# MCU.net
KiCad netlist of a schematic drawn in Altium Designer
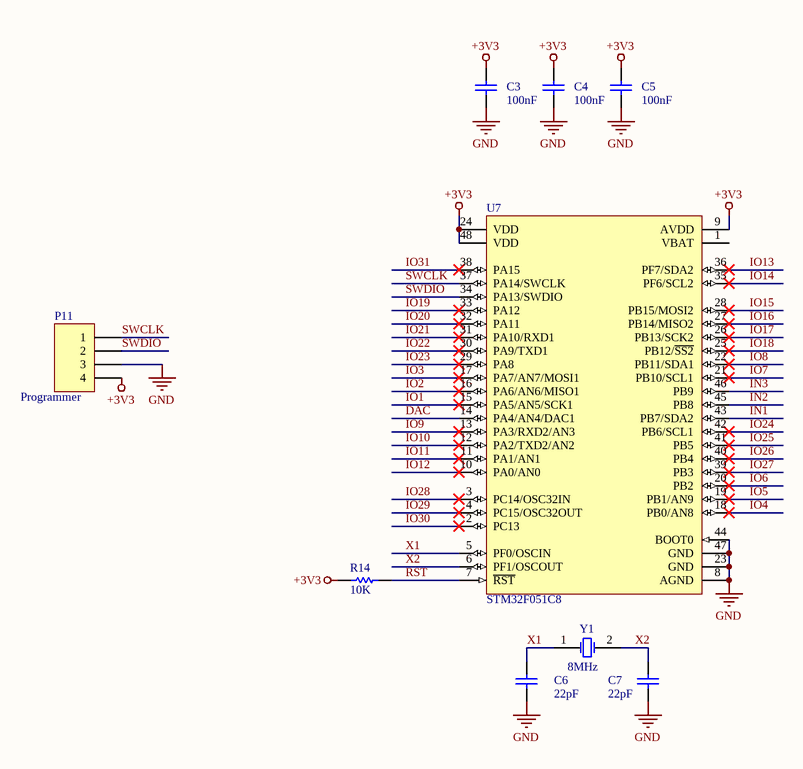
[diagram p0: MCU.SchDoc]

(export (version "E")
  (design (tool "Eeschema 10.0.6"))
  (components
    (comp (ref "C3")
      (value "100nF")
      (footprint "C-0805")
      (description "Capacitor")
      (fields (field (name "Comment") "104") (field (name "PUBLISHER") "Altium Limited"))
      (libsource (lib "Miscellaneous Devices") (part "Cap"))
    )
    (comp (ref "C4")
      (value "100nF")
      (footprint "C-0805")
      (description "Capacitor")
      (fields (field (name "Comment") "104") (field (name "PUBLISHER") "Altium Limited"))
      (libsource (lib "Miscellaneous Devices") (part "Cap"))
    )
    (comp (ref "C5")
      (value "100nF")
      (footprint "C-0805")
      (description "Capacitor")
      (fields (field (name "Comment") "104") (field (name "PUBLISHER") "Altium Limited"))
      (libsource (lib "Miscellaneous Devices") (part "Cap"))
    )
    (comp (ref "C6")
      (value "22pF")
      (footprint "C-0805")
      (description "Capacitor")
      (fields (field (name "Comment") "22") (field (name "PUBLISHER") "Altium Limited"))
      (libsource (lib "Miscellaneous Devices") (part "Cap"))
    )
    (comp (ref "C7")
      (value "22pF")
      (footprint "C-0805")
      (description "Capacitor")
      (fields (field (name "Comment") "22") (field (name "PUBLISHER") "Altium Limited"))
      (libsource (lib "Miscellaneous Devices") (part "Cap"))
    )
    (comp (ref "P11")
      (value "Programmer")
      (footprint "JP2.54-M-1x04A")
      (description "Header, 4-Pin")
      (fields (field (name "Comment") "JP2.54-M-4P"))
      (libsource (lib "Miscellaneous Connectors") (part "Header 4"))
    )
    (comp (ref "R14")
      (value "10K")
      (footprint "R-0805")
      (description "Resistor")
      (fields (field (name "PUBLISHER") "Altium Limited"))
      (libsource (lib "Miscellaneous Devices") (part "Res1"))
    )
    (comp (ref "U7")
      (value "STM32F051C8")
      (footprint "LQFP-48")
      (description "Core: ARM® 32-bit Cortex® -M0 CPU, frequency up to 48 MHz")
      (libsource (lib "Dlib") (part "STM32F051C8"))
    )
    (comp (ref "Y1")
      (value "8MHz")
      (footprint "XTAL-49S")
      (description "Crystal Oscillator")
      (libsource (lib "Miscellaneous Devices") (part "XTAL"))
    )
  )
  (nets
    (net (code "1") (name "+3V3") (class "Default")
      (node (ref "C3") (pin "1") (pinfunction "1_1") (pintype "passive"))
      (node (ref "C4") (pin "1") (pinfunction "1_1") (pintype "passive"))
      (node (ref "C5") (pin "1") (pinfunction "1_1") (pintype "passive"))
      (node (ref "P11") (pin "4") (pinfunction "4_4") (pintype "passive"))
      (node (ref "R14") (pin "2") (pinfunction "2_2") (pintype "passive"))
      (node (ref "U7") (pin "24") (pinfunction "VDD_24") (pintype "power_in"))
      (node (ref "U7") (pin "48") (pinfunction "VDD_48") (pintype "power_in"))
      (node (ref "U7") (pin "9") (pinfunction "AVDD_9") (pintype "power_in"))
    )
    (net (code "2") (name "/DAC") (class "Default")
      (node (ref "U7") (pin "14") (pinfunction "PA4/AN4/DAC1_14") (pintype "bidirectional"))
    )
    (net (code "3") (name "/IN1") (class "Default")
      (node (ref "U7") (pin "43") (pinfunction "PB7/SDA2_43") (pintype "bidirectional"))
    )
    (net (code "4") (name "/IN2") (class "Default")
      (node (ref "U7") (pin "45") (pinfunction "PB8_45") (pintype "bidirectional"))
    )
    (net (code "5") (name "/IN3") (class "Default")
      (node (ref "U7") (pin "46") (pinfunction "PB9_46") (pintype "bidirectional"))
    )
    (net (code "6") (name "/IO1") (class "Default")
      (node (ref "U7") (pin "15") (pinfunction "PA5/AN5/SCK1_15") (pintype "bidirectional+no_connect"))
    )
    (net (code "7") (name "/IO2") (class "Default")
      (node (ref "U7") (pin "16") (pinfunction "PA6/AN6/MISO1_16") (pintype "bidirectional+no_connect"))
    )
    (net (code "8") (name "/IO3") (class "Default")
      (node (ref "U7") (pin "17") (pinfunction "PA7/AN7/MOSI1_17") (pintype "bidirectional+no_connect"))
    )
    (net (code "9") (name "/IO4") (class "Default")
      (node (ref "U7") (pin "18") (pinfunction "PB0/AN8_18") (pintype "bidirectional+no_connect"))
    )
    (net (code "10") (name "/IO5") (class "Default")
      (node (ref "U7") (pin "19") (pinfunction "PB1/AN9_19") (pintype "bidirectional+no_connect"))
    )
    (net (code "11") (name "/IO6") (class "Default")
      (node (ref "U7") (pin "20") (pinfunction "PB2_20") (pintype "bidirectional+no_connect"))
    )
    (net (code "12") (name "/IO7") (class "Default")
      (node (ref "U7") (pin "21") (pinfunction "PB10/SCL1_21") (pintype "bidirectional+no_connect"))
    )
    (net (code "13") (name "/IO8") (class "Default")
      (node (ref "U7") (pin "22") (pinfunction "PB11/SDA1_22") (pintype "bidirectional+no_connect"))
    )
    (net (code "14") (name "/IO9") (class "Default")
      (node (ref "U7") (pin "13") (pinfunction "PA3/RXD2/AN3_13") (pintype "bidirectional+no_connect"))
    )
    (net (code "15") (name "/IO10") (class "Default")
      (node (ref "U7") (pin "12") (pinfunction "PA2/TXD2/AN2_12") (pintype "bidirectional+no_connect"))
    )
    (net (code "16") (name "/IO11") (class "Default")
      (node (ref "U7") (pin "11") (pinfunction "PA1/AN1_11") (pintype "bidirectional+no_connect"))
    )
    (net (code "17") (name "/IO12") (class "Default")
      (node (ref "U7") (pin "10") (pinfunction "PA0/AN0_10") (pintype "bidirectional+no_connect"))
    )
    (net (code "18") (name "/IO13") (class "Default")
      (node (ref "U7") (pin "36") (pinfunction "PF7/SDA2_36") (pintype "bidirectional+no_connect"))
    )
    (net (code "19") (name "/IO14") (class "Default")
      (node (ref "U7") (pin "35") (pinfunction "PF6/SCL2_35") (pintype "bidirectional+no_connect"))
    )
    (net (code "20") (name "/IO15") (class "Default")
      (node (ref "U7") (pin "28") (pinfunction "PB15/MOSI2_28") (pintype "bidirectional+no_connect"))
    )
    (net (code "21") (name "/IO16") (class "Default")
      (node (ref "U7") (pin "27") (pinfunction "PB14/MISO2_27") (pintype "bidirectional+no_connect"))
    )
    (net (code "22") (name "/IO17") (class "Default")
      (node (ref "U7") (pin "26") (pinfunction "PB13/SCK2_26") (pintype "bidirectional+no_connect"))
    )
    (net (code "23") (name "/IO18") (class "Default")
      (node (ref "U7") (pin "25") (pinfunction "PB12/~{SS2}_25") (pintype "bidirectional+no_connect"))
    )
    (net (code "24") (name "/IO19") (class "Default")
      (node (ref "U7") (pin "33") (pinfunction "PA12_33") (pintype "bidirectional+no_connect"))
    )
    (net (code "25") (name "/IO20") (class "Default")
      (node (ref "U7") (pin "32") (pinfunction "PA11_32") (pintype "bidirectional+no_connect"))
    )
    (net (code "26") (name "/IO21") (class "Default")
      (node (ref "U7") (pin "31") (pinfunction "PA10/RXD1_31") (pintype "bidirectional+no_connect"))
    )
    (net (code "27") (name "/IO22") (class "Default")
      (node (ref "U7") (pin "30") (pinfunction "PA9/TXD1_30") (pintype "bidirectional+no_connect"))
    )
    (net (code "28") (name "/IO23") (class "Default")
      (node (ref "U7") (pin "29") (pinfunction "PA8_29") (pintype "bidirectional+no_connect"))
    )
    (net (code "29") (name "/IO24") (class "Default")
      (node (ref "U7") (pin "42") (pinfunction "PB6/SCL1_42") (pintype "bidirectional+no_connect"))
    )
    (net (code "30") (name "/IO25") (class "Default")
      (node (ref "U7") (pin "41") (pinfunction "PB5_41") (pintype "bidirectional+no_connect"))
    )
    (net (code "31") (name "/IO26") (class "Default")
      (node (ref "U7") (pin "40") (pinfunction "PB4_40") (pintype "bidirectional+no_connect"))
    )
    (net (code "32") (name "/IO27") (class "Default")
      (node (ref "U7") (pin "39") (pinfunction "PB3_39") (pintype "bidirectional+no_connect"))
    )
    (net (code "33") (name "/IO28") (class "Default")
      (node (ref "U7") (pin "3") (pinfunction "PC14/OSC32IN_3") (pintype "bidirectional+no_connect"))
    )
    (net (code "34") (name "/IO29") (class "Default")
      (node (ref "U7") (pin "4") (pinfunction "PC15/OSC32OUT_4") (pintype "bidirectional+no_connect"))
    )
    (net (code "35") (name "/IO30") (class "Default")
      (node (ref "U7") (pin "2") (pinfunction "PC13_2") (pintype "bidirectional+no_connect"))
    )
    (net (code "36") (name "/IO31") (class "Default")
      (node (ref "U7") (pin "38") (pinfunction "PA15_38") (pintype "bidirectional+no_connect"))
    )
    (net (code "37") (name "/RST") (class "Default")
      (node (ref "R14") (pin "1") (pinfunction "1_1") (pintype "passive"))
      (node (ref "U7") (pin "7") (pinfunction "~{RST}_7") (pintype "input"))
    )
    (net (code "38") (name "/SWCLK") (class "Default")
      (node (ref "P11") (pin "1") (pinfunction "1_1") (pintype "passive"))
      (node (ref "U7") (pin "37") (pinfunction "PA14/SWCLK_37") (pintype "bidirectional"))
    )
    (net (code "39") (name "/SWDIO") (class "Default")
      (node (ref "P11") (pin "2") (pinfunction "2_2") (pintype "passive"))
      (node (ref "U7") (pin "34") (pinfunction "PA13/SWDIO_34") (pintype "bidirectional"))
    )
    (net (code "40") (name "/X1") (class "Default")
      (node (ref "C6") (pin "2") (pinfunction "2_2") (pintype "passive"))
      (node (ref "U7") (pin "5") (pinfunction "PF0/OSCIN_5") (pintype "bidirectional"))
      (node (ref "Y1") (pin "1") (pinfunction "OSC1_1") (pintype "passive"))
    )
    (net (code "41") (name "/X2") (class "Default")
      (node (ref "C7") (pin "2") (pinfunction "2_2") (pintype "passive"))
      (node (ref "U7") (pin "6") (pinfunction "PF1/OSCOUT_6") (pintype "bidirectional"))
      (node (ref "Y1") (pin "2") (pinfunction "OSC2_2") (pintype "passive"))
    )
    (net (code "42") (name "GND") (class "Default")
      (node (ref "C3") (pin "2") (pinfunction "2_2") (pintype "passive"))
      (node (ref "C4") (pin "2") (pinfunction "2_2") (pintype "passive"))
      (node (ref "C5") (pin "2") (pinfunction "2_2") (pintype "passive"))
      (node (ref "C6") (pin "1") (pinfunction "1_1") (pintype "passive"))
      (node (ref "C7") (pin "1") (pinfunction "1_1") (pintype "passive"))
      (node (ref "P11") (pin "3") (pinfunction "3_3") (pintype "passive"))
      (node (ref "U7") (pin "23") (pinfunction "GND_23") (pintype "power_in"))
      (node (ref "U7") (pin "44") (pinfunction "BOOT0_44") (pintype "input"))
      (node (ref "U7") (pin "47") (pinfunction "GND_47") (pintype "power_in"))
      (node (ref "U7") (pin "8") (pinfunction "AGND_8") (pintype "power_in"))
    )
    (net (code "43") (name "unconnected-(U7-VBAT-Pad1)") (class "Default")
      (node (ref "U7") (pin "1") (pinfunction "VBAT_1") (pintype "power_in"))
    )
  )
)
